# output_board.net
KiCad netlist of a schematic drawn in EAGLE
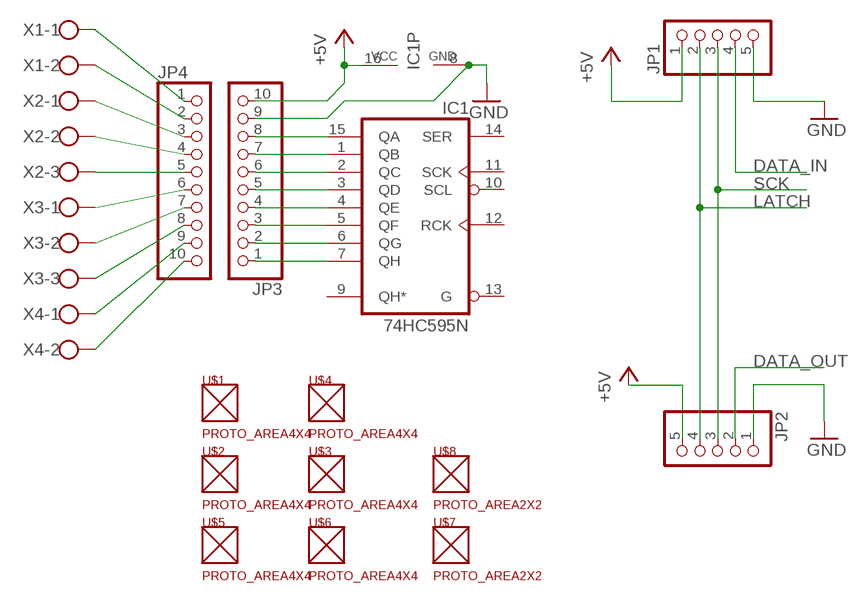
[diagram p0: schematic, sheet 1]

(export (version "E")
  (design (tool "Eeschema 10.0.6"))
  (components
    (comp (ref "IC1")
      (value "74HC595N")
      (footprint "eagle-import:DIL16")
      (libsource (lib "eagle-import") (part "74595NHC"))
    )
    (comp (ref "JP1")
      (value "PINHD-1X5")
      (footprint "eagle-import:1X05")
      (libsource (lib "eagle-import") (part "PINHD-1X5"))
    )
    (comp (ref "JP2")
      (value "PINHD-1X5")
      (footprint "eagle-import:1X05")
      (libsource (lib "eagle-import") (part "PINHD-1X5"))
    )
    (comp (ref "JP3")
      (value "PINHD-1X10")
      (footprint "eagle-import:1X10")
      (libsource (lib "eagle-import") (part "PINHD-1X10"))
    )
    (comp (ref "JP4")
      (value "PINHD-1X10")
      (footprint "eagle-import:1X10")
      (libsource (lib "eagle-import") (part "PINHD-1X10"))
    )
    (comp (ref "U$1")
      (value "PROTO_AREA4X4")
      (footprint "eagle-import:PROTO4X4")
      (libsource (lib "eagle-import") (part "PROTO_AREA4X4"))
    )
    (comp (ref "U$2")
      (value "PROTO_AREA4X4")
      (footprint "eagle-import:PROTO4X4")
      (libsource (lib "eagle-import") (part "PROTO_AREA4X4"))
    )
    (comp (ref "U$3")
      (value "PROTO_AREA4X4")
      (footprint "eagle-import:PROTO4X4")
      (libsource (lib "eagle-import") (part "PROTO_AREA4X4"))
    )
    (comp (ref "U$4")
      (value "PROTO_AREA4X4")
      (footprint "eagle-import:PROTO4X4")
      (libsource (lib "eagle-import") (part "PROTO_AREA4X4"))
    )
    (comp (ref "U$5")
      (value "PROTO_AREA4X4")
      (footprint "eagle-import:PROTO4X4")
      (libsource (lib "eagle-import") (part "PROTO_AREA4X4"))
    )
    (comp (ref "U$6")
      (value "PROTO_AREA4X4")
      (footprint "eagle-import:PROTO4X4")
      (libsource (lib "eagle-import") (part "PROTO_AREA4X4"))
    )
    (comp (ref "U$7")
      (value "PROTO_AREA2X2")
      (footprint "eagle-import:PROTO2X2")
      (libsource (lib "eagle-import") (part "PROTO_AREA2X2"))
    )
    (comp (ref "U$8")
      (value "PROTO_AREA2X2")
      (footprint "eagle-import:PROTO2X2")
      (libsource (lib "eagle-import") (part "PROTO_AREA2X2"))
    )
    (comp (ref "X1")
      (value "W237-102")
      (footprint "eagle-import:W237-102")
      (fields (field (name "MPN") "237-102"))
      (libsource (lib "eagle-import") (part "W237-102"))
    )
    (comp (ref "X2")
      (value "W237-103")
      (footprint "eagle-import:W237-103")
      (fields (field (name "MPN") "237-103"))
      (libsource (lib "eagle-import") (part "W237-103"))
    )
    (comp (ref "X3")
      (value "W237-103")
      (footprint "eagle-import:W237-103")
      (fields (field (name "MPN") "237-103"))
      (libsource (lib "eagle-import") (part "W237-103"))
    )
    (comp (ref "X4")
      (value "W237-102")
      (footprint "eagle-import:W237-102")
      (fields (field (name "MPN") "237-102"))
      (libsource (lib "eagle-import") (part "W237-102"))
    )
  )
  (nets
    (net (code "1") (name "+5V") (class "Default")
      (node (ref "IC1") (pin "16") (pinfunction "VCC_16") (pintype "power_in"))
      (node (ref "JP1") (pin "1") (pinfunction "1_1") (pintype "passive"))
      (node (ref "JP2") (pin "5") (pinfunction "5_5") (pintype "passive"))
      (node (ref "JP3") (pin "10") (pinfunction "10_10") (pintype "passive"))
    )
    (net (code "2") (name "/DATA_IN") (class "Default")
      (node (ref "JP1") (pin "4") (pinfunction "4_4") (pintype "passive"))
    )
    (net (code "3") (name "/DATA_OUT") (class "Default")
      (node (ref "JP2") (pin "2") (pinfunction "2_2") (pintype "passive"))
    )
    (net (code "4") (name "/LATCH") (class "Default")
      (node (ref "JP1") (pin "2") (pinfunction "2_2") (pintype "passive"))
      (node (ref "JP2") (pin "4") (pinfunction "4_4") (pintype "passive"))
    )
    (net (code "5") (name "/SCK") (class "Default")
      (node (ref "JP1") (pin "3") (pinfunction "3_3") (pintype "passive"))
      (node (ref "JP2") (pin "3") (pinfunction "3_3") (pintype "passive"))
    )
    (net (code "6") (name "GND") (class "Default")
      (node (ref "IC1") (pin "8") (pinfunction "GND_8") (pintype "power_in"))
      (node (ref "JP1") (pin "5") (pinfunction "5_5") (pintype "passive"))
      (node (ref "JP2") (pin "1") (pinfunction "1_1") (pintype "passive"))
      (node (ref "JP3") (pin "9") (pinfunction "9_9") (pintype "passive"))
    )
    (net (code "7") (name "Net-(IC1A-QA)") (class "Default")
      (node (ref "IC1") (pin "15") (pinfunction "QA_15") (pintype "tri_state"))
      (node (ref "JP3") (pin "8") (pinfunction "8_8") (pintype "passive"))
    )
    (net (code "8") (name "Net-(IC1A-QB)") (class "Default")
      (node (ref "IC1") (pin "1") (pinfunction "QB_1") (pintype "tri_state"))
      (node (ref "JP3") (pin "7") (pinfunction "7_7") (pintype "passive"))
    )
    (net (code "9") (name "Net-(IC1A-QC)") (class "Default")
      (node (ref "IC1") (pin "2") (pinfunction "QC_2") (pintype "tri_state"))
      (node (ref "JP3") (pin "6") (pinfunction "6_6") (pintype "passive"))
    )
    (net (code "10") (name "Net-(IC1A-QD)") (class "Default")
      (node (ref "IC1") (pin "3") (pinfunction "QD_3") (pintype "tri_state"))
      (node (ref "JP3") (pin "5") (pinfunction "5_5") (pintype "passive"))
    )
    (net (code "11") (name "Net-(IC1A-QE)") (class "Default")
      (node (ref "IC1") (pin "4") (pinfunction "QE_4") (pintype "tri_state"))
      (node (ref "JP3") (pin "4") (pinfunction "4_4") (pintype "passive"))
    )
    (net (code "12") (name "Net-(IC1A-QF)") (class "Default")
      (node (ref "IC1") (pin "5") (pinfunction "QF_5") (pintype "tri_state"))
      (node (ref "JP3") (pin "3") (pinfunction "3_3") (pintype "passive"))
    )
    (net (code "13") (name "Net-(IC1A-QG)") (class "Default")
      (node (ref "IC1") (pin "6") (pinfunction "QG_6") (pintype "tri_state"))
      (node (ref "JP3") (pin "2") (pinfunction "2_2") (pintype "passive"))
    )
    (net (code "14") (name "Net-(IC1A-QH)") (class "Default")
      (node (ref "IC1") (pin "7") (pinfunction "QH_7") (pintype "tri_state"))
      (node (ref "JP3") (pin "1") (pinfunction "1_1") (pintype "passive"))
    )
    (net (code "15") (name "Net-(X1A-KL)") (class "Default")
      (node (ref "JP4") (pin "1") (pinfunction "1_1") (pintype "passive"))
      (node (ref "X1") (pin "1") (pinfunction "KL_1") (pintype "passive"))
    )
    (net (code "16") (name "Net-(X1B-KL)") (class "Default")
      (node (ref "JP4") (pin "2") (pinfunction "2_2") (pintype "passive"))
      (node (ref "X1") (pin "2") (pinfunction "KL_2") (pintype "passive"))
    )
    (net (code "17") (name "Net-(X2A-KL)") (class "Default")
      (node (ref "JP4") (pin "3") (pinfunction "3_3") (pintype "passive"))
      (node (ref "X2") (pin "1") (pinfunction "KL_1") (pintype "passive"))
    )
    (net (code "18") (name "Net-(X2B-KL)") (class "Default")
      (node (ref "JP4") (pin "4") (pinfunction "4_4") (pintype "passive"))
      (node (ref "X2") (pin "2") (pinfunction "KL_2") (pintype "passive"))
    )
    (net (code "19") (name "Net-(X2C-KL)") (class "Default")
      (node (ref "JP4") (pin "5") (pinfunction "5_5") (pintype "passive"))
      (node (ref "X2") (pin "3") (pinfunction "KL_3") (pintype "passive"))
    )
    (net (code "20") (name "Net-(X3A-KL)") (class "Default")
      (node (ref "JP4") (pin "6") (pinfunction "6_6") (pintype "passive"))
      (node (ref "X3") (pin "1") (pinfunction "KL_1") (pintype "passive"))
    )
    (net (code "21") (name "Net-(X3B-KL)") (class "Default")
      (node (ref "JP4") (pin "7") (pinfunction "7_7") (pintype "passive"))
      (node (ref "X3") (pin "2") (pinfunction "KL_2") (pintype "passive"))
    )
    (net (code "22") (name "Net-(X3C-KL)") (class "Default")
      (node (ref "JP4") (pin "8") (pinfunction "8_8") (pintype "passive"))
      (node (ref "X3") (pin "3") (pinfunction "KL_3") (pintype "passive"))
    )
    (net (code "23") (name "Net-(X4A-KL)") (class "Default")
      (node (ref "JP4") (pin "9") (pinfunction "9_9") (pintype "passive"))
      (node (ref "X4") (pin "1") (pinfunction "KL_1") (pintype "passive"))
    )
    (net (code "24") (name "Net-(X4B-KL)") (class "Default")
      (node (ref "JP4") (pin "10") (pinfunction "10_10") (pintype "passive"))
      (node (ref "X4") (pin "2") (pinfunction "KL_2") (pintype "passive"))
    )
    (net (code "25") (name "unconnected-(IC1A-G-Pad13)") (class "Default")
      (node (ref "IC1") (pin "13") (pinfunction "G_13") (pintype "input"))
    )
    (net (code "26") (name "unconnected-(IC1A-QH*-Pad9)") (class "Default")
      (node (ref "IC1") (pin "9") (pinfunction "QH*_9") (pintype "tri_state"))
    )
    (net (code "27") (name "unconnected-(IC1A-RCK-Pad12)") (class "Default")
      (node (ref "IC1") (pin "12") (pinfunction "RCK_12") (pintype "input"))
    )
    (net (code "28") (name "unconnected-(IC1A-SCK-Pad11)") (class "Default")
      (node (ref "IC1") (pin "11") (pinfunction "SCK_11") (pintype "input"))
    )
    (net (code "29") (name "unconnected-(IC1A-SCL-Pad10)") (class "Default")
      (node (ref "IC1") (pin "10") (pinfunction "SCL_10") (pintype "input"))
    )
    (net (code "30") (name "unconnected-(IC1A-SER-Pad14)") (class "Default")
      (node (ref "IC1") (pin "14") (pinfunction "SER_14") (pintype "input"))
    )
  )
)
